# PULSE_OXIMETER_SHIELD.net
KiCad netlist of a schematic drawn in EAGLE
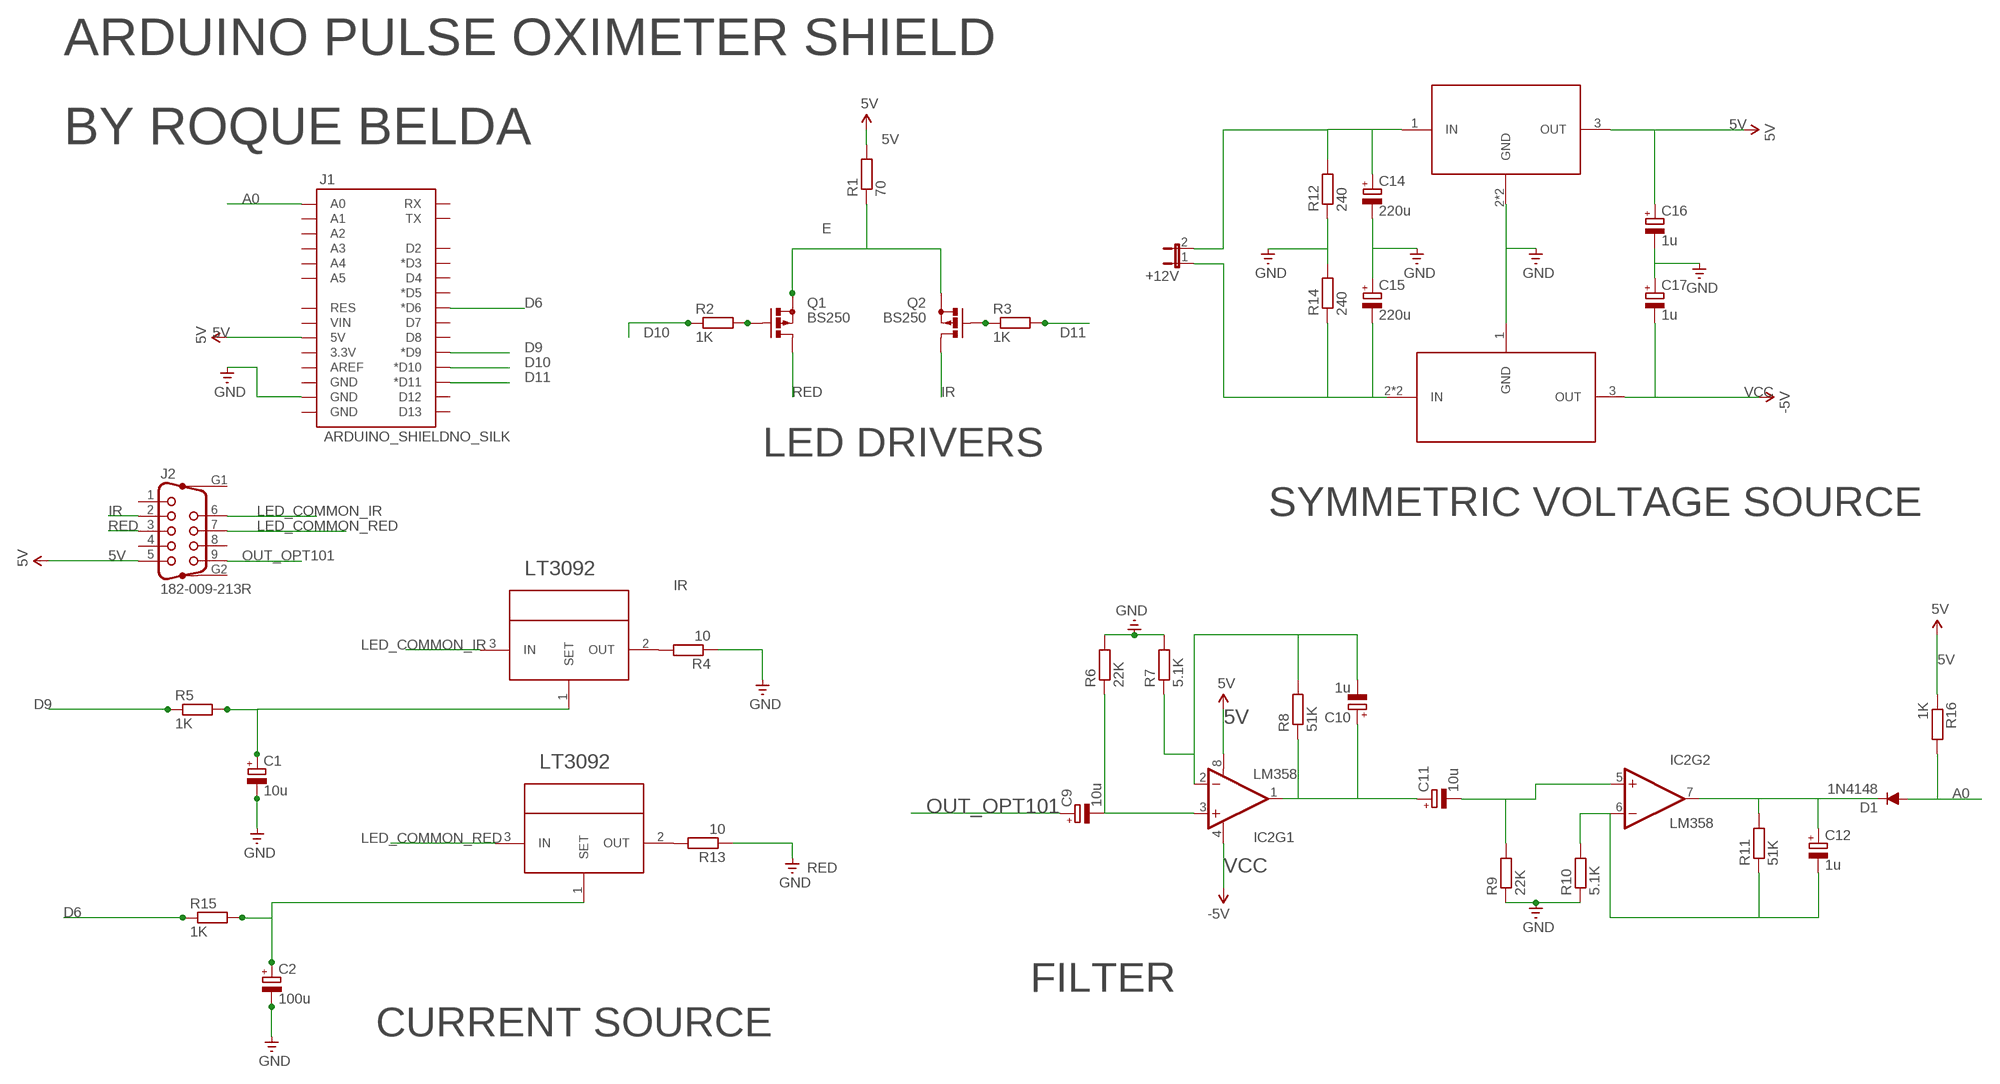
[diagram p0: schematic, sheet 1]

(export (version "E")
  (design (tool "Eeschema 10.0.6"))
  (components
    (comp (ref "+12V")
      (value "JP1E")
      (footprint "eagle-import:JP1")
      (libsource (lib "eagle-import") (part "JP1E"))
    )
    (comp (ref "C1")
      (value "10u")
      (footprint "eagle-import:E2,5-6")
      (libsource (lib "eagle-import") (part "CPOL-EUE2.5-6"))
    )
    (comp (ref "C2")
      (value "100u")
      (footprint "eagle-import:E2,5-6")
      (libsource (lib "eagle-import") (part "CPOL-EUE2.5-6"))
    )
    (comp (ref "C9")
      (value "10u")
      (footprint "eagle-import:E2,5-6")
      (libsource (lib "eagle-import") (part "CPOL-EUE2.5-6"))
    )
    (comp (ref "C10")
      (value "1u")
      (footprint "eagle-import:E2,5-6")
      (libsource (lib "eagle-import") (part "CPOL-EUE2.5-6"))
    )
    (comp (ref "C11")
      (value "10u")
      (footprint "eagle-import:E2,5-6")
      (libsource (lib "eagle-import") (part "CPOL-EUE2.5-6"))
    )
    (comp (ref "C12")
      (value "1u")
      (footprint "eagle-import:E2,5-6")
      (libsource (lib "eagle-import") (part "CPOL-EUE2.5-6"))
    )
    (comp (ref "C14")
      (value "220u")
      (footprint "eagle-import:E3,5-8")
      (libsource (lib "eagle-import") (part "CPOL-EUE3.5-8"))
    )
    (comp (ref "C15")
      (value "220u")
      (footprint "eagle-import:E3,5-8")
      (libsource (lib "eagle-import") (part "CPOL-EUE3.5-8"))
    )
    (comp (ref "C16")
      (value "1u")
      (footprint "eagle-import:E2,5-6")
      (libsource (lib "eagle-import") (part "CPOL-EUE2.5-6"))
    )
    (comp (ref "C17")
      (value "1u")
      (footprint "eagle-import:E2,5-6")
      (libsource (lib "eagle-import") (part "CPOL-EUE2.5-6"))
    )
    (comp (ref "D1")
      (value "1N4148")
      (footprint "eagle-import:DO35-10")
      (libsource (lib "eagle-import") (part "1N4148"))
    )
    (comp (ref "IC2")
      (value "LM358")
      (footprint "eagle-import:DIP08")
      (libsource (lib "eagle-import") (part "LM358"))
    )
    (comp (ref "J1")
      (value "ARDUINO_SHIELDNO_SILK")
      (footprint "eagle-import:DUEMILANOVE_VIAS")
      (libsource (lib "eagle-import") (part "ARDUINO_SHIELDNO_SILK"))
    )
    (comp (ref "J2")
      (value "182-009-213R")
      (footprint "eagle-import:182-009-213R")
      (libsource (lib "eagle-import") (part "182-009-213R"))
    )
    (comp (ref "Q1")
      (value "BS250")
      (footprint "eagle-import:SOT54E")
      (libsource (lib "eagle-import") (part "BS250"))
    )
    (comp (ref "Q2")
      (value "BS250")
      (footprint "eagle-import:SOT54E")
      (libsource (lib "eagle-import") (part "BS250"))
    )
    (comp (ref "R1")
      (value "70")
      (footprint "eagle-import:0204_5")
      (libsource (lib "eagle-import") (part "R-EU_0204/5"))
    )
    (comp (ref "R2")
      (value "1K")
      (footprint "eagle-import:0204_5")
      (libsource (lib "eagle-import") (part "R-EU_0204/5"))
    )
    (comp (ref "R3")
      (value "1K")
      (footprint "eagle-import:0204_5")
      (libsource (lib "eagle-import") (part "R-EU_0204/5"))
    )
    (comp (ref "R4")
      (value "10")
      (footprint "eagle-import:0204_5")
      (libsource (lib "eagle-import") (part "R-EU_0204/5"))
    )
    (comp (ref "R5")
      (value "1K")
      (footprint "eagle-import:0204_5")
      (libsource (lib "eagle-import") (part "R-EU_0204/5"))
    )
    (comp (ref "R6")
      (value "22K")
      (footprint "eagle-import:0204_5")
      (libsource (lib "eagle-import") (part "R-EU_0204/5"))
    )
    (comp (ref "R7")
      (value "5.1K")
      (footprint "eagle-import:0204_5")
      (libsource (lib "eagle-import") (part "R-EU_0204/5"))
    )
    (comp (ref "R8")
      (value "51K")
      (footprint "eagle-import:0204_5")
      (libsource (lib "eagle-import") (part "R-EU_0204/5"))
    )
    (comp (ref "R9")
      (value "22K")
      (footprint "eagle-import:0204_5")
      (libsource (lib "eagle-import") (part "R-EU_0204/5"))
    )
    (comp (ref "R10")
      (value "5.1K")
      (footprint "eagle-import:0204_5")
      (libsource (lib "eagle-import") (part "R-EU_0204/5"))
    )
    (comp (ref "R11")
      (value "51K")
      (footprint "eagle-import:0204_5")
      (libsource (lib "eagle-import") (part "R-EU_0204/5"))
    )
    (comp (ref "R12")
      (value "240")
      (footprint "eagle-import:0204_5")
      (libsource (lib "eagle-import") (part "R-EU_0204/5"))
    )
    (comp (ref "R13")
      (value "10")
      (footprint "eagle-import:0204_5")
      (libsource (lib "eagle-import") (part "R-EU_0204/5"))
    )
    (comp (ref "R14")
      (value "240")
      (footprint "eagle-import:0204_5")
      (libsource (lib "eagle-import") (part "R-EU_0204/5"))
    )
    (comp (ref "R15")
      (value "1K")
      (footprint "eagle-import:0204_5")
      (libsource (lib "eagle-import") (part "R-EU_0204/5"))
    )
    (comp (ref "R16")
      (value "1K")
      (footprint "eagle-import:0204_5")
      (libsource (lib "eagle-import") (part "R-EU_0204/5"))
    )
    (comp (ref "U$1")
      (value "LT3092")
      (footprint "eagle-import:SOT223")
      (libsource (lib "eagle-import") (part "LT3092"))
    )
    (comp (ref "U$2")
      (value "UA78M05")
      (footprint "eagle-import:SOT223")
      (libsource (lib "eagle-import") (part "UA78M05"))
    )
    (comp (ref "U$3")
      (value "UA79M05")
      (footprint "eagle-import:TO263-3")
      (libsource (lib "eagle-import") (part "UA79M05"))
    )
    (comp (ref "U$4")
      (value "LT3092")
      (footprint "eagle-import:SOT223")
      (libsource (lib "eagle-import") (part "LT3092"))
    )
  )
  (nets
    (net (code "1") (name "-5V") (class "Default")
      (node (ref "C17") (pin "-") (pinfunction "-_-") (pintype "passive"))
      (node (ref "IC2") (pin "4") (pinfunction "V-_4") (pintype "power_in"))
      (node (ref "U$3") (pin "3") (pinfunction "OUT_3") (pintype "output"))
    )
    (net (code "2") (name "/A0") (class "Default")
      (node (ref "D1") (pin "A") (pinfunction "A_A") (pintype "passive"))
      (node (ref "J1") (pin "A0") (pinfunction "A0_A0") (pintype "bidirectional"))
      (node (ref "R16") (pin "2") (pinfunction "2_2") (pintype "passive"))
    )
    (net (code "3") (name "/D6") (class "Default")
      (node (ref "J1") (pin "D6") (pinfunction "*D6_D6") (pintype "bidirectional"))
      (node (ref "R15") (pin "1") (pinfunction "1_1") (pintype "passive"))
    )
    (net (code "4") (name "/D9") (class "Default")
      (node (ref "J1") (pin "D9") (pinfunction "*D9_D9") (pintype "bidirectional"))
      (node (ref "R5") (pin "1") (pinfunction "1_1") (pintype "passive"))
    )
    (net (code "5") (name "/D10") (class "Default")
      (node (ref "J1") (pin "D10") (pinfunction "*D10_D10") (pintype "bidirectional"))
      (node (ref "R2") (pin "1") (pinfunction "1_1") (pintype "passive"))
    )
    (net (code "6") (name "/D11") (class "Default")
      (node (ref "J1") (pin "D11") (pinfunction "*D11_D11") (pintype "bidirectional"))
      (node (ref "R3") (pin "2") (pinfunction "2_2") (pintype "passive"))
    )
    (net (code "7") (name "/E") (class "Default")
      (node (ref "Q1") (pin "S") (pinfunction "S_S") (pintype "passive"))
      (node (ref "Q2") (pin "S") (pinfunction "S_S") (pintype "passive"))
      (node (ref "R1") (pin "1") (pinfunction "1_1") (pintype "passive"))
    )
    (net (code "8") (name "/IR") (class "Default")
      (node (ref "J2") (pin "2") (pinfunction "2_2") (pintype "passive"))
      (node (ref "Q2") (pin "D") (pinfunction "D_D") (pintype "passive"))
    )
    (net (code "9") (name "/LED_COMMON_IR") (class "Default")
      (node (ref "J2") (pin "6") (pinfunction "6_6") (pintype "passive"))
      (node (ref "U$1") (pin "3") (pinfunction "IN_3") (pintype "input"))
    )
    (net (code "10") (name "/LED_COMMON_RED") (class "Default")
      (node (ref "J2") (pin "7") (pinfunction "7_7") (pintype "passive"))
      (node (ref "U$4") (pin "3") (pinfunction "IN_3") (pintype "input"))
    )
    (net (code "11") (name "/OUT_OPT101") (class "Default")
      (node (ref "C9") (pin "+") (pinfunction "+_+") (pintype "passive"))
      (node (ref "J2") (pin "9") (pinfunction "9_9") (pintype "passive"))
    )
    (net (code "12") (name "/RED") (class "Default")
      (node (ref "J2") (pin "3") (pinfunction "3_3") (pintype "passive"))
      (node (ref "Q1") (pin "D") (pinfunction "D_D") (pintype "passive"))
    )
    (net (code "13") (name "5V") (class "Default")
      (node (ref "C16") (pin "+") (pinfunction "+_+") (pintype "passive"))
      (node (ref "IC2") (pin "8") (pinfunction "V+_8") (pintype "power_in"))
      (node (ref "J1") (pin "5V") (pinfunction "5V_5V") (pintype "bidirectional"))
      (node (ref "J2") (pin "5") (pinfunction "5_5") (pintype "passive"))
      (node (ref "R1") (pin "2") (pinfunction "2_2") (pintype "passive"))
      (node (ref "R16") (pin "1") (pinfunction "1_1") (pintype "passive"))
      (node (ref "U$2") (pin "3") (pinfunction "OUT_3") (pintype "output"))
    )
    (net (code "14") (name "GND") (class "Default")
      (node (ref "C1") (pin "-") (pinfunction "-_-") (pintype "passive"))
      (node (ref "C14") (pin "-") (pinfunction "-_-") (pintype "passive"))
      (node (ref "C15") (pin "+") (pinfunction "+_+") (pintype "passive"))
      (node (ref "C2") (pin "-") (pinfunction "-_-") (pintype "passive"))
      (node (ref "J1") (pin "GND@1") (pinfunction "GND_GND@1") (pintype "bidirectional"))
      (node (ref "R10") (pin "1") (pinfunction "1_1") (pintype "passive"))
      (node (ref "R13") (pin "1") (pinfunction "1_1") (pintype "passive"))
      (node (ref "R4") (pin "1") (pinfunction "1_1") (pintype "passive"))
      (node (ref "R6") (pin "2") (pinfunction "2_2") (pintype "passive"))
      (node (ref "R7") (pin "2") (pinfunction "2_2") (pintype "passive"))
      (node (ref "R9") (pin "1") (pinfunction "1_1") (pintype "passive"))
      (node (ref "U$2") (pin "2") (pinfunction "GND_2") (pintype "input"))
      (node (ref "U$2") (pin "4") (pinfunction "GND_4") (pintype "input"))
      (node (ref "U$3") (pin "1") (pinfunction "GND_1") (pintype "input"))
    )
    (net (code "15") (name "Net-(+12V-Pad1)") (class "Default")
      (node (ref "+12V") (pin "1") (pinfunction "1_1") (pintype "passive"))
      (node (ref "C15") (pin "-") (pinfunction "-_-") (pintype "passive"))
      (node (ref "R14") (pin "1") (pinfunction "1_1") (pintype "passive"))
      (node (ref "U$3") (pin "2") (pinfunction "IN_2") (pintype "input"))
      (node (ref "U$3") (pin "4") (pinfunction "IN_4") (pintype "input"))
    )
    (net (code "16") (name "Net-(C16-Pad-)") (class "Default")
      (node (ref "C16") (pin "-") (pinfunction "-_-") (pintype "passive"))
      (node (ref "C17") (pin "+") (pinfunction "+_+") (pintype "passive"))
    )
    (net (code "17") (name "Net-(IC2A-+IN)") (class "Default")
      (node (ref "C9") (pin "-") (pinfunction "-_-") (pintype "passive"))
      (node (ref "IC2") (pin "3") (pinfunction "+IN_3") (pintype "input"))
      (node (ref "R6") (pin "1") (pinfunction "1_1") (pintype "passive"))
    )
    (net (code "18") (name "Net-(IC2A--IN)") (class "Default")
      (node (ref "C10") (pin "-") (pinfunction "-_-") (pintype "passive"))
      (node (ref "IC2") (pin "2") (pinfunction "-IN_2") (pintype "input"))
      (node (ref "R7") (pin "1") (pinfunction "1_1") (pintype "passive"))
      (node (ref "R8") (pin "2") (pinfunction "2_2") (pintype "passive"))
    )
    (net (code "19") (name "Net-(IC2A-OUT)") (class "Default")
      (node (ref "C10") (pin "+") (pinfunction "+_+") (pintype "passive"))
      (node (ref "C11") (pin "+") (pinfunction "+_+") (pintype "passive"))
      (node (ref "IC2") (pin "1") (pinfunction "OUT_1") (pintype "output"))
      (node (ref "R8") (pin "1") (pinfunction "1_1") (pintype "passive"))
    )
    (net (code "20") (name "Net-(IC2B-+IN)") (class "Default")
      (node (ref "C11") (pin "-") (pinfunction "-_-") (pintype "passive"))
      (node (ref "IC2") (pin "5") (pinfunction "+IN_5") (pintype "input"))
      (node (ref "R9") (pin "2") (pinfunction "2_2") (pintype "passive"))
    )
    (net (code "21") (name "Net-(IC2B--IN)") (class "Default")
      (node (ref "C12") (pin "-") (pinfunction "-_-") (pintype "passive"))
      (node (ref "IC2") (pin "6") (pinfunction "-IN_6") (pintype "input"))
      (node (ref "R10") (pin "2") (pinfunction "2_2") (pintype "passive"))
      (node (ref "R11") (pin "1") (pinfunction "1_1") (pintype "passive"))
    )
    (net (code "22") (name "Net-(IC2B-OUT)") (class "Default")
      (node (ref "C12") (pin "+") (pinfunction "+_+") (pintype "passive"))
      (node (ref "D1") (pin "C") (pinfunction "C_C") (pintype "passive"))
      (node (ref "IC2") (pin "7") (pinfunction "OUT_7") (pintype "output"))
      (node (ref "R11") (pin "2") (pinfunction "2_2") (pintype "passive"))
    )
    (net (code "23") (name "Net-(Q1-PadG)") (class "Default")
      (node (ref "Q1") (pin "G") (pinfunction "G_G") (pintype "passive"))
      (node (ref "R2") (pin "2") (pinfunction "2_2") (pintype "passive"))
    )
    (net (code "24") (name "Net-(Q2-PadG)") (class "Default")
      (node (ref "Q2") (pin "G") (pinfunction "G_G") (pintype "passive"))
      (node (ref "R3") (pin "1") (pinfunction "1_1") (pintype "passive"))
    )
    (net (code "25") (name "Net-(R12-Pad1)") (class "Default")
      (node (ref "R12") (pin "1") (pinfunction "1_1") (pintype "passive"))
      (node (ref "R14") (pin "2") (pinfunction "2_2") (pintype "passive"))
    )
    (net (code "26") (name "Net-(U$1-OUT)") (class "Default")
      (node (ref "R4") (pin "2") (pinfunction "2_2") (pintype "passive"))
      (node (ref "U$1") (pin "2") (pinfunction "OUT_2") (pintype "output"))
    )
    (net (code "27") (name "Net-(U$1-SET)") (class "Default")
      (node (ref "C1") (pin "+") (pinfunction "+_+") (pintype "passive"))
      (node (ref "R5") (pin "2") (pinfunction "2_2") (pintype "passive"))
      (node (ref "U$1") (pin "1") (pinfunction "SET_1") (pintype "input"))
    )
    (net (code "28") (name "Net-(U$2-IN)") (class "Default")
      (node (ref "+12V") (pin "2") (pinfunction "2_2") (pintype "passive"))
      (node (ref "C14") (pin "+") (pinfunction "+_+") (pintype "passive"))
      (node (ref "R12") (pin "2") (pinfunction "2_2") (pintype "passive"))
      (node (ref "U$2") (pin "1") (pinfunction "IN_1") (pintype "input"))
    )
    (net (code "29") (name "Net-(U$4-OUT)") (class "Default")
      (node (ref "R13") (pin "2") (pinfunction "2_2") (pintype "passive"))
      (node (ref "U$4") (pin "2") (pinfunction "OUT_2") (pintype "output"))
    )
    (net (code "30") (name "Net-(U$4-SET)") (class "Default")
      (node (ref "C2") (pin "+") (pinfunction "+_+") (pintype "passive"))
      (node (ref "R15") (pin "2") (pinfunction "2_2") (pintype "passive"))
      (node (ref "U$4") (pin "1") (pinfunction "SET_1") (pintype "input"))
    )
    (net (code "31") (name "unconnected-(J1-*D3-PadD3)") (class "Default")
      (node (ref "J1") (pin "D3") (pinfunction "*D3_D3") (pintype "bidirectional"))
    )
    (net (code "32") (name "unconnected-(J1-*D5-PadD5)") (class "Default")
      (node (ref "J1") (pin "D5") (pinfunction "*D5_D5") (pintype "bidirectional"))
    )
    (net (code "33") (name "unconnected-(J1-GND-PadGND@0)") (class "Default")
      (node (ref "J1") (pin "GND@0") (pinfunction "GND_GND@0") (pintype "bidirectional"))
    )
    (net (code "34") (name "unconnected-(J1-GND-PadGND@2)") (class "Default")
      (node (ref "J1") (pin "GND@2") (pinfunction "GND_GND@2") (pintype "bidirectional"))
    )
    (net (code "35") (name "unconnected-(J1-Pad3.3V)") (class "Default")
      (node (ref "J1") (pin "3.3V") (pinfunction "3.3V_3.3V") (pintype "bidirectional"))
    )
    (net (code "36") (name "unconnected-(J1-PadA1)") (class "Default")
      (node (ref "J1") (pin "A1") (pinfunction "A1_A1") (pintype "bidirectional"))
    )
    (net (code "37") (name "unconnected-(J1-PadA2)") (class "Default")
      (node (ref "J1") (pin "A2") (pinfunction "A2_A2") (pintype "bidirectional"))
    )
    (net (code "38") (name "unconnected-(J1-PadA3)") (class "Default")
      (node (ref "J1") (pin "A3") (pinfunction "A3_A3") (pintype "bidirectional"))
    )
    (net (code "39") (name "unconnected-(J1-PadA4)") (class "Default")
      (node (ref "J1") (pin "A4") (pinfunction "A4_A4") (pintype "bidirectional"))
    )
    (net (code "40") (name "unconnected-(J1-PadA5)") (class "Default")
      (node (ref "J1") (pin "A5") (pinfunction "A5_A5") (pintype "bidirectional"))
    )
    (net (code "41") (name "unconnected-(J1-PadAREF)") (class "Default")
      (node (ref "J1") (pin "AREF") (pinfunction "AREF_AREF") (pintype "bidirectional"))
    )
    (net (code "42") (name "unconnected-(J1-PadD2)") (class "Default")
      (node (ref "J1") (pin "D2") (pinfunction "D2_D2") (pintype "bidirectional"))
    )
    (net (code "43") (name "unconnected-(J1-PadD4)") (class "Default")
      (node (ref "J1") (pin "D4") (pinfunction "D4_D4") (pintype "bidirectional"))
    )
    (net (code "44") (name "unconnected-(J1-PadD7)") (class "Default")
      (node (ref "J1") (pin "D7") (pinfunction "D7_D7") (pintype "bidirectional"))
    )
    (net (code "45") (name "unconnected-(J1-PadD8)") (class "Default")
      (node (ref "J1") (pin "D8") (pinfunction "D8_D8") (pintype "bidirectional"))
    )
    (net (code "46") (name "unconnected-(J1-PadD12)") (class "Default")
      (node (ref "J1") (pin "D12") (pinfunction "D12_D12") (pintype "bidirectional"))
    )
    (net (code "47") (name "unconnected-(J1-PadD13)") (class "Default")
      (node (ref "J1") (pin "D13") (pinfunction "D13_D13") (pintype "bidirectional"))
    )
    (net (code "48") (name "unconnected-(J1-PadRES)") (class "Default")
      (node (ref "J1") (pin "RES") (pinfunction "RES_RES") (pintype "bidirectional"))
    )
    (net (code "49") (name "unconnected-(J1-PadRX)") (class "Default")
      (node (ref "J1") (pin "RX") (pinfunction "RX_RX") (pintype "bidirectional"))
    )
    (net (code "50") (name "unconnected-(J1-PadTX)") (class "Default")
      (node (ref "J1") (pin "TX") (pinfunction "TX_TX") (pintype "bidirectional"))
    )
    (net (code "51") (name "unconnected-(J1-PadVIN)") (class "Default")
      (node (ref "J1") (pin "VIN") (pinfunction "VIN_VIN") (pintype "bidirectional"))
    )
    (net (code "52") (name "unconnected-(J2-Pad1)") (class "Default")
      (node (ref "J2") (pin "1") (pinfunction "1_1") (pintype "passive"))
    )
    (net (code "53") (name "unconnected-(J2-Pad4)") (class "Default")
      (node (ref "J2") (pin "4") (pinfunction "4_4") (pintype "passive"))
    )
    (net (code "54") (name "unconnected-(J2-Pad8)") (class "Default")
      (node (ref "J2") (pin "8") (pinfunction "8_8") (pintype "passive"))
    )
    (net (code "55") (name "unconnected-(J2-PadG1)") (class "Default")
      (node (ref "J2") (pin "G1") (pinfunction "G1_G1") (pintype "passive"))
    )
    (net (code "56") (name "unconnected-(J2-PadG2)") (class "Default")
      (node (ref "J2") (pin "G2") (pinfunction "G2_G2") (pintype "passive"))
    )
  )
)
